# ESC.net
KiCad netlist of a schematic drawn in EasyEDA Pro
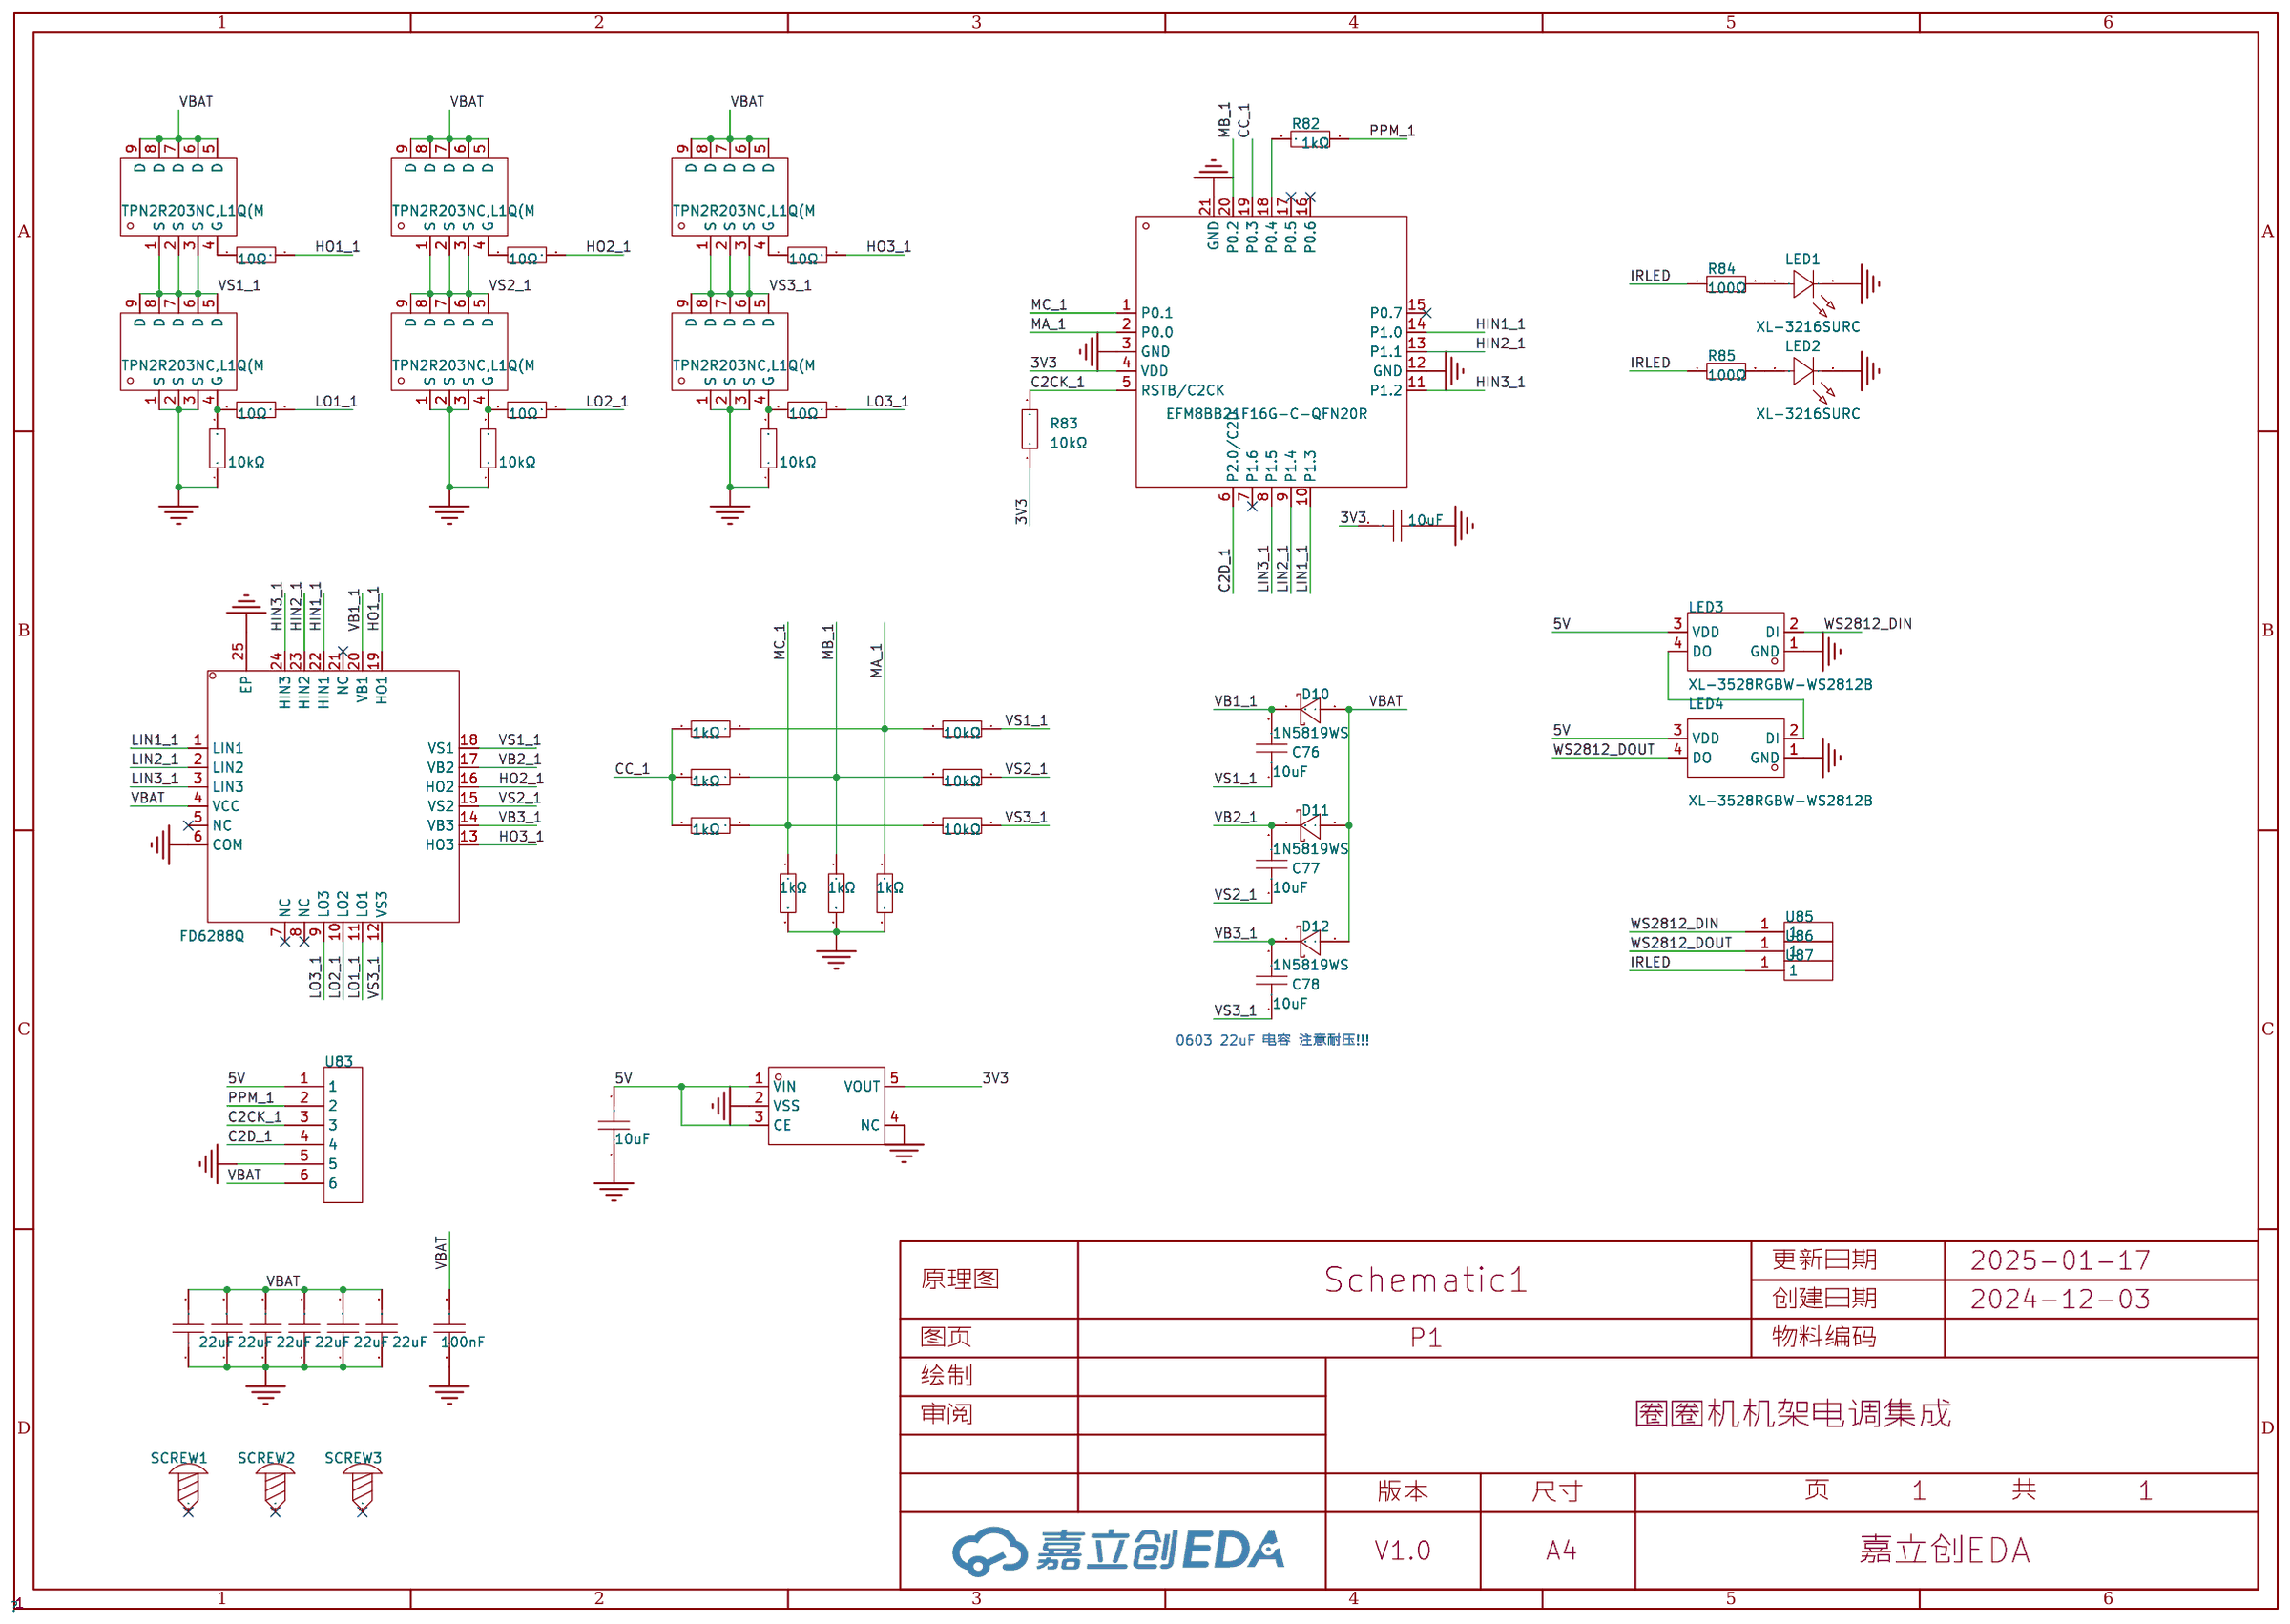
[diagram p0: schematic sheet]

(export (version "E")
  (design (tool "Eeschema 10.0.6"))
  (components
    (comp (ref "C6")
      (value "10uF")
      (footprint "easyedapro:C0603")
      (fields
        (field (name "Manufacturer Part") "CL10A106KP8NNNC")
        (field (name "Manufacturer") "SAMSUNG(三星)")
      )
      (libsource (lib "easyedapro") (part "CapAcitance"))
    )
    (comp (ref "C34")
      (value "100nF")
      (footprint "easyedapro:C0603")
      (fields
        (field (name "Manufacturer Part") "CC0603KRX7R9BB104")
        (field (name "Manufacturer") "YAGEO(国巨)")
      )
      (libsource (lib "easyedapro") (part "CapAcitance"))
    )
    (comp (ref "C45")
      (value "22uF")
      (footprint "easyedapro:C0805")
      (description "容值:22uF;精度:±20%;额定电压:25V;材质(温度系数):X5R;")
      (fields
        (field (name "Manufacturer Part") "CL21A226MAQNNNE")
        (field (name "Manufacturer") "SAMSUNG(三星)")
      )
      (libsource (lib "easyedapro") (part "CL21A226MAQNNNE"))
    )
    (comp (ref "C73")
      (value "22uF")
      (footprint "easyedapro:C0805")
      (description "容值:22uF;精度:±20%;额定电压:25V;材质(温度系数):X5R;")
      (fields
        (field (name "Manufacturer Part") "CL21A226MAQNNNE")
        (field (name "Manufacturer") "SAMSUNG(三星)")
      )
      (libsource (lib "easyedapro") (part "CL21A226MAQNNNE"))
    )
    (comp (ref "C74")
      (value "22uF")
      (footprint "easyedapro:C0805")
      (description "容值:22uF;精度:±20%;额定电压:25V;材质(温度系数):X5R;")
      (fields
        (field (name "Manufacturer Part") "CL21A226MAQNNNE")
        (field (name "Manufacturer") "SAMSUNG(三星)")
      )
      (libsource (lib "easyedapro") (part "CL21A226MAQNNNE"))
    )
    (comp (ref "C75")
      (value "10uF")
      (footprint "easyedapro:C0603")
      (fields
        (field (name "Manufacturer Part") "CL10A106KP8NNNC")
        (field (name "Manufacturer") "SAMSUNG(三星)")
      )
      (libsource (lib "easyedapro") (part "CapAcitance"))
    )
    (comp (ref "C76")
      (value "10uF")
      (footprint "easyedapro:C0603")
      (fields
        (field (name "Manufacturer Part") "CL10A106MA8NRNC")
        (field (name "Manufacturer") "SAMSUNG(三星)")
      )
      (libsource (lib "easyedapro") (part "CapAcitance"))
    )
    (comp (ref "C77")
      (value "10uF")
      (footprint "easyedapro:C0603")
      (fields
        (field (name "Manufacturer Part") "CL10A106MA8NRNC")
        (field (name "Manufacturer") "SAMSUNG(三星)")
      )
      (libsource (lib "easyedapro") (part "CapAcitance"))
    )
    (comp (ref "C78")
      (value "10uF")
      (footprint "easyedapro:C0603")
      (fields
        (field (name "Manufacturer Part") "CL10A106MA8NRNC")
        (field (name "Manufacturer") "SAMSUNG(三星)")
      )
      (libsource (lib "easyedapro") (part "CapAcitance"))
    )
    (comp (ref "C79")
      (value "22uF")
      (footprint "easyedapro:C0805")
      (description "容值:22uF;精度:±20%;额定电压:25V;材质(温度系数):X5R;")
      (fields
        (field (name "Manufacturer Part") "CL21A226MAQNNNE")
        (field (name "Manufacturer") "SAMSUNG(三星)")
      )
      (libsource (lib "easyedapro") (part "CL21A226MAQNNNE"))
    )
    (comp (ref "C80")
      (value "22uF")
      (footprint "easyedapro:C0805")
      (description "容值:22uF;精度:±20%;额定电压:25V;材质(温度系数):X5R;")
      (fields
        (field (name "Manufacturer Part") "CL21A226MAQNNNE")
        (field (name "Manufacturer") "SAMSUNG(三星)")
      )
      (libsource (lib "easyedapro") (part "CL21A226MAQNNNE"))
    )
    (comp (ref "C81")
      (value "22uF")
      (footprint "easyedapro:C0805")
      (description "容值:22uF;精度:±20%;额定电压:25V;材质(温度系数):X5R;")
      (fields
        (field (name "Manufacturer Part") "CL21A226MAQNNNE")
        (field (name "Manufacturer") "SAMSUNG(三星)")
      )
      (libsource (lib "easyedapro") (part "CL21A226MAQNNNE"))
    )
    (comp (ref "D10")
      (value "1N5819WS")
      (footprint "easyedapro:SOD-323_L1.8-W1.3-LS2.5-RD")
      (description "正向压降(Vf):600mV@1A;直流反向耐压(Vr):40V;平均整流电流(Io):1A;")
      (fields (field (name "Manufacturer") "Hottech(合科泰)"))
      (libsource (lib "easyedapro") (part "1N5819WS"))
    )
    (comp (ref "D11")
      (value "1N5819WS")
      (footprint "easyedapro:SOD-323_L1.8-W1.3-LS2.5-RD")
      (description "正向压降(Vf):600mV@1A;直流反向耐压(Vr):40V;平均整流电流(Io):1A;")
      (fields (field (name "Manufacturer") "Hottech(合科泰)"))
      (libsource (lib "easyedapro") (part "1N5819WS"))
    )
    (comp (ref "D12")
      (value "1N5819WS")
      (footprint "easyedapro:SOD-323_L1.8-W1.3-LS2.5-RD")
      (description "正向压降(Vf):600mV@1A;直流反向耐压(Vr):40V;平均整流电流(Io):1A;")
      (fields (field (name "Manufacturer") "Hottech(合科泰)"))
      (libsource (lib "easyedapro") (part "1N5819WS"))
    )
    (comp (ref "LED1")
      (value "XL-3216SURC")
      (footprint "easyedapro:LED1206-R-RD_RED")
      (description "发光颜色:红色;功率:55mW;正向电流:25mA;主波长:617nm~621nm;透镜颜色:无色透明透镜;色温:-;发光角度:120°;载带方式:正贴;工作温度:-30°C~+85°C;")
      (fields (field (name "Manufacturer") "XINGLIGHT(成兴光)"))
      (libsource (lib "easyedapro") (part "XL-3216SURC"))
    )
    (comp (ref "LED2")
      (value "XL-3216SURC")
      (footprint "easyedapro:LED1206-R-RD_RED")
      (description "发光颜色:红色;功率:55mW;正向电流:25mA;主波长:617nm~621nm;透镜颜色:无色透明透镜;色温:-;发光角度:120°;载带方式:正贴;工作温度:-30°C~+85°C;")
      (fields (field (name "Manufacturer") "XINGLIGHT(成兴光)"))
      (libsource (lib "easyedapro") (part "XL-3216SURC"))
    )
    (comp (ref "LED3")
      (value "XL-3528RGBW-WS2812B")
      (footprint "easyedapro:LED-SMD_4P-L3.5-W2.8-BR-1")
      (description "3528 七彩幻彩雾状 ws2812B 内置驱动IC")
      (fields (field (name "Manufacturer") "XINGLIGHT(成兴光)"))
      (libsource (lib "easyedapro") (part "XL-3528RGBW-WS2812B"))
    )
    (comp (ref "LED4")
      (value "XL-3528RGBW-WS2812B")
      (footprint "easyedapro:LED-SMD_4P-L3.5-W2.8-BR-1")
      (description "3528 七彩幻彩雾状 ws2812B 内置驱动IC")
      (fields (field (name "Manufacturer") "XINGLIGHT(成兴光)"))
      (libsource (lib "easyedapro") (part "XL-3528RGBW-WS2812B"))
    )
    (comp (ref "Q7")
      (value "TPN2R203NC,L1Q(M")
      (footprint "easyedapro:TSON-8_L3.1-W3.1-P0.65-LS3.3-BL-EP")
      (fields (field (name "Manufacturer") "TOSHIBA(东芝)"))
      (libsource (lib "easyedapro") (part "TPN2R203NC,L1Q(M"))
    )
    (comp (ref "Q8")
      (value "TPN2R203NC,L1Q(M")
      (footprint "easyedapro:TSON-8_L3.1-W3.1-P0.65-LS3.3-BL-EP")
      (fields (field (name "Manufacturer") "TOSHIBA(东芝)"))
      (libsource (lib "easyedapro") (part "TPN2R203NC,L1Q(M"))
    )
    (comp (ref "Q9")
      (value "TPN2R203NC,L1Q(M")
      (footprint "easyedapro:TSON-8_L3.1-W3.1-P0.65-LS3.3-BL-EP")
      (fields (field (name "Manufacturer") "TOSHIBA(东芝)"))
      (libsource (lib "easyedapro") (part "TPN2R203NC,L1Q(M"))
    )
    (comp (ref "Q10")
      (value "TPN2R203NC,L1Q(M")
      (footprint "easyedapro:TSON-8_L3.1-W3.1-P0.65-LS3.3-BL-EP")
      (fields (field (name "Manufacturer") "TOSHIBA(东芝)"))
      (libsource (lib "easyedapro") (part "TPN2R203NC,L1Q(M"))
    )
    (comp (ref "Q11")
      (value "TPN2R203NC,L1Q(M")
      (footprint "easyedapro:TSON-8_L3.1-W3.1-P0.65-LS3.3-BL-EP")
      (fields (field (name "Manufacturer") "TOSHIBA(东芝)"))
      (libsource (lib "easyedapro") (part "TPN2R203NC,L1Q(M"))
    )
    (comp (ref "Q12")
      (value "TPN2R203NC,L1Q(M")
      (footprint "easyedapro:TSON-8_L3.1-W3.1-P0.65-LS3.3-BL-EP")
      (fields (field (name "Manufacturer") "TOSHIBA(东芝)"))
      (libsource (lib "easyedapro") (part "TPN2R203NC,L1Q(M"))
    )
    (comp (ref "R62")
      (value "10Ω")
      (footprint "easyedapro:R0402")
      (fields
        (field (name "Manufacturer Part") "0402WGF100JTCE")
        (field (name "Manufacturer") "UNI-ROYAL(厚声)")
      )
      (libsource (lib "easyedapro") (part "电阻"))
    )
    (comp (ref "R63")
      (value "10Ω")
      (footprint "easyedapro:R0402")
      (fields
        (field (name "Manufacturer Part") "0402WGF100JTCE")
        (field (name "Manufacturer") "UNI-ROYAL(厚声)")
      )
      (libsource (lib "easyedapro") (part "电阻"))
    )
    (comp (ref "R64")
      (value "10Ω")
      (footprint "easyedapro:R0402")
      (fields
        (field (name "Manufacturer Part") "0402WGF100JTCE")
        (field (name "Manufacturer") "UNI-ROYAL(厚声)")
      )
      (libsource (lib "easyedapro") (part "电阻"))
    )
    (comp (ref "R65")
      (value "10Ω")
      (footprint "easyedapro:R0402")
      (fields
        (field (name "Manufacturer Part") "0402WGF100JTCE")
        (field (name "Manufacturer") "UNI-ROYAL(厚声)")
      )
      (libsource (lib "easyedapro") (part "电阻"))
    )
    (comp (ref "R66")
      (value "10Ω")
      (footprint "easyedapro:R0402")
      (fields
        (field (name "Manufacturer Part") "0402WGF100JTCE")
        (field (name "Manufacturer") "UNI-ROYAL(厚声)")
      )
      (libsource (lib "easyedapro") (part "电阻"))
    )
    (comp (ref "R67")
      (value "10Ω")
      (footprint "easyedapro:R0402")
      (fields
        (field (name "Manufacturer Part") "0402WGF100JTCE")
        (field (name "Manufacturer") "UNI-ROYAL(厚声)")
      )
      (libsource (lib "easyedapro") (part "电阻"))
    )
    (comp (ref "R68")
      (value "10kΩ")
      (footprint "easyedapro:R0402")
      (fields
        (field (name "Manufacturer Part") "0402WGF1002TCE")
        (field (name "Manufacturer") "UNI-ROYAL(厚声)")
      )
      (libsource (lib "easyedapro") (part "电阻"))
    )
    (comp (ref "R69")
      (value "10kΩ")
      (footprint "easyedapro:R0402")
      (fields
        (field (name "Manufacturer Part") "0402WGF1002TCE")
        (field (name "Manufacturer") "UNI-ROYAL(厚声)")
      )
      (libsource (lib "easyedapro") (part "电阻"))
    )
    (comp (ref "R70")
      (value "10kΩ")
      (footprint "easyedapro:R0402")
      (fields
        (field (name "Manufacturer Part") "0402WGF1002TCE")
        (field (name "Manufacturer") "UNI-ROYAL(厚声)")
      )
      (libsource (lib "easyedapro") (part "电阻"))
    )
    (comp (ref "R71")
      (value "10kΩ")
      (footprint "easyedapro:R0402")
      (fields
        (field (name "Manufacturer Part") "0402WGF1002TCE")
        (field (name "Manufacturer") "UNI-ROYAL(厚声)")
      )
      (libsource (lib "easyedapro") (part "电阻"))
    )
    (comp (ref "R72")
      (value "10kΩ")
      (footprint "easyedapro:R0402")
      (fields
        (field (name "Manufacturer Part") "0402WGF1002TCE")
        (field (name "Manufacturer") "UNI-ROYAL(厚声)")
      )
      (libsource (lib "easyedapro") (part "电阻"))
    )
    (comp (ref "R73")
      (value "10kΩ")
      (footprint "easyedapro:R0402")
      (fields
        (field (name "Manufacturer Part") "0402WGF1002TCE")
        (field (name "Manufacturer") "UNI-ROYAL(厚声)")
      )
      (libsource (lib "easyedapro") (part "电阻"))
    )
    (comp (ref "R74")
      (value "1kΩ")
      (footprint "easyedapro:R0402")
      (fields
        (field (name "Manufacturer Part") "0402WGF1001TCE")
        (field (name "Manufacturer") "UNI-ROYAL(厚声)")
      )
      (libsource (lib "easyedapro") (part "电阻"))
    )
    (comp (ref "R75")
      (value "1kΩ")
      (footprint "easyedapro:R0402")
      (fields
        (field (name "Manufacturer Part") "0402WGF1001TCE")
        (field (name "Manufacturer") "UNI-ROYAL(厚声)")
      )
      (libsource (lib "easyedapro") (part "电阻"))
    )
    (comp (ref "R76")
      (value "1kΩ")
      (footprint "easyedapro:R0402")
      (fields
        (field (name "Manufacturer Part") "0402WGF1001TCE")
        (field (name "Manufacturer") "UNI-ROYAL(厚声)")
      )
      (libsource (lib "easyedapro") (part "电阻"))
    )
    (comp (ref "R77")
      (value "1kΩ")
      (footprint "easyedapro:R0402")
      (fields
        (field (name "Manufacturer Part") "0402WGF1001TCE")
        (field (name "Manufacturer") "UNI-ROYAL(厚声)")
      )
      (libsource (lib "easyedapro") (part "电阻"))
    )
    (comp (ref "R78")
      (value "1kΩ")
      (footprint "easyedapro:R0402")
      (fields
        (field (name "Manufacturer Part") "0402WGF1001TCE")
        (field (name "Manufacturer") "UNI-ROYAL(厚声)")
      )
      (libsource (lib "easyedapro") (part "电阻"))
    )
    (comp (ref "R79")
      (value "1kΩ")
      (footprint "easyedapro:R0402")
      (fields
        (field (name "Manufacturer Part") "0402WGF1001TCE")
        (field (name "Manufacturer") "UNI-ROYAL(厚声)")
      )
      (libsource (lib "easyedapro") (part "电阻"))
    )
    (comp (ref "R82")
      (value "1kΩ")
      (footprint "easyedapro:R0402")
      (fields
        (field (name "Manufacturer Part") "0603WAF1001T5E")
        (field (name "Manufacturer") "UNI-ROYAL(厚声)")
      )
      (libsource (lib "easyedapro") (part "电阻"))
    )
    (comp (ref "R83")
      (value "10kΩ")
      (footprint "easyedapro:R0402")
      (fields
        (field (name "Manufacturer Part") "0603WAF1002T5E")
        (field (name "Manufacturer") "UNI-ROYAL(厚声)")
      )
      (libsource (lib "easyedapro") (part "电阻"))
    )
    (comp (ref "R84")
      (value "100Ω")
      (footprint "easyedapro:R0402")
      (fields
        (field (name "Manufacturer Part") "0603WAF1000T5E")
        (field (name "Manufacturer") "UNI-ROYAL(厚声)")
      )
      (libsource (lib "easyedapro") (part "电阻"))
    )
    (comp (ref "R85")
      (value "100Ω")
      (footprint "easyedapro:R0402")
      (fields
        (field (name "Manufacturer Part") "0603WAF1000T5E")
        (field (name "Manufacturer") "UNI-ROYAL(厚声)")
      )
      (libsource (lib "easyedapro") (part "电阻"))
    )
    (comp (ref "SCREW1")
      (value "~")
      (footprint "easyedapro:M2螺丝")
      (libsource (lib "easyedapro") (part "螺丝孔"))
    )
    (comp (ref "SCREW2")
      (value "~")
      (footprint "easyedapro:M2螺丝")
      (libsource (lib "easyedapro") (part "螺丝孔"))
    )
    (comp (ref "SCREW3")
      (value "~")
      (footprint "easyedapro:M2螺丝")
      (libsource (lib "easyedapro") (part "螺丝孔"))
    )
    (comp (ref "U2")
      (value "EFM8BB21F16G-C-QFN20R")
      (footprint "easyedapro:QFN-20_L3.0-W3.0-P0.50-BL-EP1.7_EFM8BB21F16G")
      (description "CPU内核:51系列;程序存储容量:16KB;RAM总容量:2.25KB;GPIO端口数量:16;工作电压范围:2.2V~3.6V;CPU最大主频:50MHz;程序存储器类型:FLASH;")
      (fields (field (name "Manufacturer") "SKYWORKS/SILICON LABS(芯科)"))
      (libsource (lib "easyedapro") (part "EFM8BB21F16G-C-QFN20"))
    )
    (comp (ref "U79")
      (value "ME6217C33M5G")
      (footprint "easyedapro:SOT-23-5_L3.0-W1.7-P0.95-LS2.8-BR")
      (description "输出类型:固定;输出极性:正;最大输入电压:7V;输出电压:3.3V;输出电流:800mA;电源纹波抑制比(PSRR):65dB@(1kHz);")
      (fields (field (name "Manufacturer") "MICRONE(南京微盟)"))
      (libsource (lib "easyedapro") (part "ME6217C33M5G"))
    )
    (comp (ref "U82")
      (value "FD6288Q")
      (footprint "easyedapro:QFN-24_L4.0-W4.0-P0.50-BL-EP2.6")
      (fields (field (name "Manufacturer") "Fortior Tech(峰岹)"))
      (libsource (lib "easyedapro") (part "FD6288Q_C328453"))
    )
    (comp (ref "U83")
      (value "~")
      (footprint "easyedapro:6pin焊接引出")
      (libsource (lib "easyedapro") (part "6pin焊接引出"))
    )
    (comp (ref "U85")
      (value "~")
      (footprint "easyedapro:1pin焊接引出")
      (libsource (lib "easyedapro") (part "1pin焊接引出"))
    )
    (comp (ref "U86")
      (value "~")
      (footprint "easyedapro:1pin焊接引出")
      (libsource (lib "easyedapro") (part "1pin焊接引出"))
    )
    (comp (ref "U87")
      (value "~")
      (footprint "easyedapro:1pin焊接引出")
      (libsource (lib "easyedapro") (part "1pin焊接引出"))
    )
  )
  (nets
    (net (code "1") (name "/3V3") (class "Default")
      (node (ref "C6") (pin "2") (pinfunction "2_2") (pintype "input"))
      (node (ref "R83") (pin "1") (pinfunction "1_1") (pintype "input"))
      (node (ref "U2") (pin "4") (pinfunction "VDD_4") (pintype "unspecified"))
      (node (ref "U79") (pin "5") (pinfunction "VOUT_5") (pintype "input"))
    )
    (net (code "2") (name "/5V") (class "Default")
      (node (ref "C75") (pin "2") (pinfunction "2_2") (pintype "input"))
      (node (ref "LED3") (pin "3") (pinfunction "VDD_3") (pintype "unspecified"))
      (node (ref "LED4") (pin "3") (pinfunction "VDD_3") (pintype "unspecified"))
      (node (ref "U79") (pin "1") (pinfunction "VIN_1") (pintype "input"))
      (node (ref "U79") (pin "3") (pinfunction "CE_3") (pintype "input"))
      (node (ref "U83") (pin "1") (pinfunction "1_1") (pintype "input"))
    )
    (net (code "3") (name "/C2CK_1") (class "Default")
      (node (ref "R83") (pin "2") (pinfunction "2_2") (pintype "input"))
      (node (ref "U2") (pin "5") (pinfunction "RSTB/C2CK_5") (pintype "unspecified"))
      (node (ref "U83") (pin "3") (pinfunction "3_3") (pintype "input"))
    )
    (net (code "4") (name "/C2D_1") (class "Default")
      (node (ref "U2") (pin "6") (pinfunction "P2.0/C2D_6") (pintype "unspecified"))
      (node (ref "U83") (pin "4") (pinfunction "4_4") (pintype "input"))
    )
    (net (code "5") (name "/CC_1") (class "Default")
      (node (ref "R74") (pin "2") (pinfunction "2_2") (pintype "input"))
      (node (ref "R75") (pin "2") (pinfunction "2_2") (pintype "input"))
      (node (ref "R76") (pin "2") (pinfunction "2_2") (pintype "input"))
      (node (ref "U2") (pin "19") (pinfunction "P0.3_19") (pintype "unspecified"))
    )
    (net (code "6") (name "/HIN1_1") (class "Default")
      (node (ref "U2") (pin "14") (pinfunction "P1.0_14") (pintype "unspecified"))
      (node (ref "U82") (pin "22") (pinfunction "HIN1_22") (pintype "unspecified"))
    )
    (net (code "7") (name "/HIN2_1") (class "Default")
      (node (ref "U2") (pin "13") (pinfunction "P1.1_13") (pintype "unspecified"))
      (node (ref "U82") (pin "23") (pinfunction "HIN2_23") (pintype "unspecified"))
    )
    (net (code "8") (name "/HIN3_1") (class "Default")
      (node (ref "U2") (pin "11") (pinfunction "P1.2_11") (pintype "unspecified"))
      (node (ref "U82") (pin "24") (pinfunction "HIN3_24") (pintype "unspecified"))
    )
    (net (code "9") (name "/HO1_1") (class "Default")
      (node (ref "R62") (pin "2") (pinfunction "2_2") (pintype "input"))
      (node (ref "U82") (pin "19") (pinfunction "HO1_19") (pintype "unspecified"))
    )
    (net (code "10") (name "/HO2_1") (class "Default")
      (node (ref "R63") (pin "2") (pinfunction "2_2") (pintype "input"))
      (node (ref "U82") (pin "16") (pinfunction "HO2_16") (pintype "unspecified"))
    )
    (net (code "11") (name "/HO3_1") (class "Default")
      (node (ref "R64") (pin "2") (pinfunction "2_2") (pintype "input"))
      (node (ref "U82") (pin "13") (pinfunction "HO3_13") (pintype "unspecified"))
    )
    (net (code "12") (name "/IRLED") (class "Default")
      (node (ref "R84") (pin "1") (pinfunction "1_1") (pintype "input"))
      (node (ref "R85") (pin "1") (pinfunction "1_1") (pintype "input"))
      (node (ref "U87") (pin "1") (pinfunction "1_1") (pintype "input"))
    )
    (net (code "13") (name "/LIN1_1") (class "Default")
      (node (ref "U2") (pin "10") (pinfunction "P1.3_10") (pintype "unspecified"))
      (node (ref "U82") (pin "1") (pinfunction "LIN1_1") (pintype "unspecified"))
    )
    (net (code "14") (name "/LIN2_1") (class "Default")
      (node (ref "U2") (pin "9") (pinfunction "P1.4_9") (pintype "unspecified"))
      (node (ref "U82") (pin "2") (pinfunction "LIN2_2") (pintype "unspecified"))
    )
    (net (code "15") (name "/LIN3_1") (class "Default")
      (node (ref "U2") (pin "8") (pinfunction "P1.5_8") (pintype "unspecified"))
      (node (ref "U82") (pin "3") (pinfunction "LIN3_3") (pintype "unspecified"))
    )
    (net (code "16") (name "/LO1_1") (class "Default")
      (node (ref "R67") (pin "2") (pinfunction "2_2") (pintype "input"))
      (node (ref "U82") (pin "11") (pinfunction "LO1_11") (pintype "unspecified"))
    )
    (net (code "17") (name "/LO2_1") (class "Default")
      (node (ref "R66") (pin "2") (pinfunction "2_2") (pintype "input"))
      (node (ref "U82") (pin "10") (pinfunction "LO2_10") (pintype "unspecified"))
    )
    (net (code "18") (name "/LO3_1") (class "Default")
      (node (ref "R65") (pin "2") (pinfunction "2_2") (pintype "input"))
      (node (ref "U82") (pin "9") (pinfunction "LO3_9") (pintype "unspecified"))
    )
    (net (code "19") (name "/MA_1") (class "Default")
      (node (ref "R71") (pin "2") (pinfunction "2_2") (pintype "input"))
      (node (ref "R74") (pin "1") (pinfunction "1_1") (pintype "input"))
      (node (ref "R79") (pin "1") (pinfunction "1_1") (pintype "input"))
      (node (ref "U2") (pin "2") (pinfunction "P0.0_2") (pintype "unspecified"))
    )
    (net (code "20") (name "/MB_1") (class "Default")
      (node (ref "R72") (pin "2") (pinfunction "2_2") (pintype "input"))
      (node (ref "R75") (pin "1") (pinfunction "1_1") (pintype "input"))
      (node (ref "R78") (pin "1") (pinfunction "1_1") (pintype "input"))
      (node (ref "U2") (pin "20") (pinfunction "P0.2_20") (pintype "unspecified"))
    )
    (net (code "21") (name "/MC_1") (class "Default")
      (node (ref "R73") (pin "2") (pinfunction "2_2") (pintype "input"))
      (node (ref "R76") (pin "1") (pinfunction "1_1") (pintype "input"))
      (node (ref "R77") (pin "1") (pinfunction "1_1") (pintype "input"))
      (node (ref "U2") (pin "1") (pinfunction "P0.1_1") (pintype "unspecified"))
    )
    (net (code "22") (name "/PPM_1") (class "Default")
      (node (ref "R82") (pin "2") (pinfunction "2_2") (pintype "input"))
      (node (ref "U83") (pin "2") (pinfunction "2_2") (pintype "input"))
    )
    (net (code "23") (name "/VB1_1") (class "Default")
      (node (ref "C76") (pin "2") (pinfunction "2_2") (pintype "input"))
      (node (ref "D10") (pin "1") (pinfunction "K_1") (pintype "unspecified"))
      (node (ref "U82") (pin "20") (pinfunction "VB1_20") (pintype "unspecified"))
    )
    (net (code "24") (name "/VB2_1") (class "Default")
      (node (ref "C77") (pin "2") (pinfunction "2_2") (pintype "input"))
      (node (ref "D11") (pin "1") (pinfunction "K_1") (pintype "unspecified"))
      (node (ref "U82") (pin "17") (pinfunction "VB2_17") (pintype "unspecified"))
    )
    (net (code "25") (name "/VB3_1") (class "Default")
      (node (ref "C78") (pin "2") (pinfunction "2_2") (pintype "input"))
      (node (ref "D12") (pin "1") (pinfunction "K_1") (pintype "unspecified"))
      (node (ref "U82") (pin "14") (pinfunction "VB3_14") (pintype "unspecified"))
    )
    (net (code "26") (name "/VBAT") (class "Default")
      (node (ref "C34") (pin "2") (pinfunction "2_2") (pintype "input"))
      (node (ref "C45") (pin "2") (pinfunction "2_2") (pintype "unspecified"))
      (node (ref "C73") (pin "2") (pinfunction "2_2") (pintype "unspecified"))
      (node (ref "C74") (pin "2") (pinfunction "2_2") (pintype "unspecified"))
      (node (ref "C79") (pin "2") (pinfunction "2_2") (pintype "unspecified"))
      (node (ref "C80") (pin "2") (pinfunction "2_2") (pintype "unspecified"))
      (node (ref "C81") (pin "2") (pinfunction "2_2") (pintype "unspecified"))
      (node (ref "D10") (pin "2") (pinfunction "A_2") (pintype "unspecified"))
      (node (ref "D11") (pin "2") (pinfunction "A_2") (pintype "unspecified"))
      (node (ref "D12") (pin "2") (pinfunction "A_2") (pintype "unspecified"))
      (node (ref "Q11") (pin "5") (pinfunction "D_5") (pintype "unspecified"))
      (node (ref "Q11") (pin "6") (pinfunction "D_6") (pintype "unspecified"))
      (node (ref "Q11") (pin "7") (pinfunction "D_7") (pintype "unspecified"))
      (node (ref "Q11") (pin "8") (pinfunction "D_8") (pintype "unspecified"))
      (node (ref "Q11") (pin "9") (pinfunction "D_9") (pintype "unspecified"))
      (node (ref "Q7") (pin "5") (pinfunction "D_5") (pintype "unspecified"))
      (node (ref "Q7") (pin "6") (pinfunction "D_6") (pintype "unspecified"))
      (node (ref "Q7") (pin "7") (pinfunction "D_7") (pintype "unspecified"))
      (node (ref "Q7") (pin "8") (pinfunction "D_8") (pintype "unspecified"))
      (node (ref "Q7") (pin "9") (pinfunction "D_9") (pintype "unspecified"))
      (node (ref "Q9") (pin "5") (pinfunction "D_5") (pintype "unspecified"))
      (node (ref "Q9") (pin "6") (pinfunction "D_6") (pintype "unspecified"))
      (node (ref "Q9") (pin "7") (pinfunction "D_7") (pintype "unspecified"))
      (node (ref "Q9") (pin "8") (pinfunction "D_8") (pintype "unspecified"))
      (node (ref "Q9") (pin "9") (pinfunction "D_9") (pintype "unspecified"))
      (node (ref "U82") (pin "4") (pinfunction "VCC_4") (pintype "unspecified"))
      (node (ref "U83") (pin "6") (pinfunction "6_6") (pintype "input"))
    )
    (net (code "27") (name "/VS1_1") (class "Default")
      (node (ref "C76") (pin "1") (pinfunction "1_1") (pintype "input"))
      (node (ref "Q7") (pin "1") (pinfunction "S_1") (pintype "unspecified"))
      (node (ref "Q7") (pin "2") (pinfunction "S_2") (pintype "unspecified"))
      (node (ref "Q7") (pin "3") (pinfunction "S_3") (pintype "unspecified"))
      (node (ref "Q8") (pin "5") (pinfunction "D_5") (pintype "unspecified"))
      (node (ref "Q8") (pin "6") (pinfunction "D_6") (pintype "unspecified"))
      (node (ref "Q8") (pin "7") (pinfunction "D_7") (pintype "unspecified"))
      (node (ref "Q8") (pin "8") (pinfunction "D_8") (pintype "unspecified"))
      (node (ref "Q8") (pin "9") (pinfunction "D_9") (pintype "unspecified"))
      (node (ref "R71") (pin "1") (pinfunction "1_1") (pintype "input"))
      (node (ref "U82") (pin "18") (pinfunction "VS1_18") (pintype "unspecified"))
    )
    (net (code "28") (name "/VS2_1") (class "Default")
      (node (ref "C77") (pin "1") (pinfunction "1_1") (pintype "input"))
      (node (ref "Q10") (pin "5") (pinfunction "D_5") (pintype "unspecified"))
      (node (ref "Q10") (pin "6") (pinfunction "D_6") (pintype "unspecified"))
      (node (ref "Q10") (pin "7") (pinfunction "D_7") (pintype "unspecified"))
      (node (ref "Q10") (pin "8") (pinfunction "D_8") (pintype "unspecified"))
      (node (ref "Q10") (pin "9") (pinfunction "D_9") (pintype "unspecified"))
      (node (ref "Q9") (pin "1") (pinfunction "S_1") (pintype "unspecified"))
      (node (ref "Q9") (pin "2") (pinfunction "S_2") (pintype "unspecified"))
      (node (ref "Q9") (pin "3") (pinfunction "S_3") (pintype "unspecified"))
      (node (ref "R72") (pin "1") (pinfunction "1_1") (pintype "input"))
      (node (ref "U82") (pin "15") (pinfunction "VS2_15") (pintype "unspecified"))
    )
    (net (code "29") (name "/VS3_1") (class "Default")
      (node (ref "C78") (pin "1") (pinfunction "1_1") (pintype "input"))
      (node (ref "Q11") (pin "1") (pinfunction "S_1") (pintype "unspecified"))
      (node (ref "Q11") (pin "2") (pinfunction "S_2") (pintype "unspecified"))
      (node (ref "Q11") (pin "3") (pinfunction "S_3") (pintype "unspecified"))
      (node (ref "Q12") (pin "5") (pinfunction "D_5") (pintype "unspecified"))
      (node (ref "Q12") (pin "6") (pinfunction "D_6") (pintype "unspecified"))
      (node (ref "Q12") (pin "7") (pinfunction "D_7") (pintype "unspecified"))
      (node (ref "Q12") (pin "8") (pinfunction "D_8") (pintype "unspecified"))
      (node (ref "Q12") (pin "9") (pinfunction "D_9") (pintype "unspecified"))
      (node (ref "R73") (pin "1") (pinfunction "1_1") (pintype "input"))
      (node (ref "U82") (pin "12") (pinfunction "VS3_12") (pintype "unspecified"))
    )
    (net (code "30") (name "/WS2812_DIN") (class "Default")
      (node (ref "LED3") (pin "2") (pinfunction "DI_2") (pintype "unspecified"))
      (node (ref "U85") (pin "1") (pinfunction "1_1") (pintype "input"))
    )
    (net (code "31") (name "/WS2812_DOUT") (class "Default")
      (node (ref "LED4") (pin "4") (pinfunction "DO_4") (pintype "unspecified"))
      (node (ref "U86") (pin "1") (pinfunction "1_1") (pintype "input"))
    )
    (net (code "32") (name "GND") (class "Default")
      (node (ref "C34") (pin "1") (pinfunction "1_1") (pintype "input"))
      (node (ref "C45") (pin "1") (pinfunction "1_1") (pintype "unspecified"))
      (node (ref "C6") (pin "1") (pinfunction "1_1") (pintype "input"))
      (node (ref "C73") (pin "1") (pinfunction "1_1") (pintype "unspecified"))
      (node (ref "C74") (pin "1") (pinfunction "1_1") (pintype "unspecified"))
      (node (ref "C75") (pin "1") (pinfunction "1_1") (pintype "input"))
      (node (ref "C79") (pin "1") (pinfunction "1_1") (pintype "unspecified"))
      (node (ref "C80") (pin "1") (pinfunction "1_1") (pintype "unspecified"))
      (node (ref "C81") (pin "1") (pinfunction "1_1") (pintype "unspecified"))
      (node (ref "LED1") (pin "2") (pinfunction "A_2") (pintype "unspecified"))
      (node (ref "LED2") (pin "2") (pinfunction "A_2") (pintype "unspecified"))
      (node (ref "LED3") (pin "1") (pinfunction "GND_1") (pintype "unspecified"))
      (node (ref "LED4") (pin "1") (pinfunction "GND_1") (pintype "unspecified"))
      (node (ref "Q10") (pin "1") (pinfunction "S_1") (pintype "unspecified"))
      (node (ref "Q10") (pin "2") (pinfunction "S_2") (pintype "unspecified"))
      (node (ref "Q10") (pin "3") (pinfunction "S_3") (pintype "unspecified"))
      (node (ref "Q12") (pin "1") (pinfunction "S_1") (pintype "unspecified"))
      (node (ref "Q12") (pin "2") (pinfunction "S_2") (pintype "unspecified"))
      (node (ref "Q12") (pin "3") (pinfunction "S_3") (pintype "unspecified"))
      (node (ref "Q8") (pin "1") (pinfunction "S_1") (pintype "unspecified"))
      (node (ref "Q8") (pin "2") (pinfunction "S_2") (pintype "unspecified"))
      (node (ref "Q8") (pin "3") (pinfunction "S_3") (pintype "unspecified"))
      (node (ref "R68") (pin "1") (pinfunction "1_1") (pintype "input"))
      (node (ref "R69") (pin "1") (pinfunction "1_1") (pintype "input"))
      (node (ref "R70") (pin "1") (pinfunction "1_1") (pintype "input"))
      (node (ref "R77") (pin "2") (pinfunction "2_2") (pintype "input"))
      (node (ref "R78") (pin "2") (pinfunction "2_2") (pintype "input"))
      (node (ref "R79") (pin "2") (pinfunction "2_2") (pintype "input"))
      (node (ref "U2") (pin "12") (pinfunction "GND_12") (pintype "unspecified"))
      (node (ref "U2") (pin "21") (pinfunction "GND_21") (pintype "unspecified"))
      (node (ref "U2") (pin "3") (pinfunction "GND_3") (pintype "unspecified"))
      (node (ref "U79") (pin "2") (pinfunction "VSS_2") (pintype "input"))
      (node (ref "U79") (pin "4") (pinfunction "NC_4") (pintype "input"))
      (node (ref "U82") (pin "25") (pinfunction "EP_25") (pintype "unspecified"))
      (node (ref "U82") (pin "6") (pinfunction "COM_6") (pintype "unspecified"))
      (node (ref "U83") (pin "5") (pinfunction "5_5") (pintype "input"))
    )
    (net (code "33") (name "Net-(LED1-K)") (class "Default")
      (node (ref "LED1") (pin "1") (pinfunction "K_1") (pintype "unspecified"))
      (node (ref "R84") (pin "2") (pinfunction "2_2") (pintype "input"))
    )
    (net (code "34") (name "Net-(LED2-K)") (class "Default")
      (node (ref "LED2") (pin "1") (pinfunction "K_1") (pintype "unspecified"))
      (node (ref "R85") (pin "2") (pinfunction "2_2") (pintype "input"))
    )
    (net (code "35") (name "Net-(LED3-DO)") (class "Default")
      (node (ref "LED3") (pin "4") (pinfunction "DO_4") (pintype "unspecified"))
      (node (ref "LED4") (pin "2") (pinfunction "DI_2") (pintype "unspecified"))
    )
    (net (code "36") (name "Net-(Q7-G)") (class "Default")
      (node (ref "Q7") (pin "4") (pinfunction "G_4") (pintype "unspecified"))
      (node (ref "R62") (pin "1") (pinfunction "1_1") (pintype "input"))
    )
    (net (code "37") (name "Net-(Q8-G)") (class "Default")
      (node (ref "Q8") (pin "4") (pinfunction "G_4") (pintype "unspecified"))
      (node (ref "R67") (pin "1") (pinfunction "1_1") (pintype "input"))
      (node (ref "R68") (pin "2") (pinfunction "2_2") (pintype "input"))
    )
    (net (code "38") (name "Net-(Q9-G)") (class "Default")
      (node (ref "Q9") (pin "4") (pinfunction "G_4") (pintype "unspecified"))
      (node (ref "R63") (pin "1") (pinfunction "1_1") (pintype "input"))
    )
    (net (code "39") (name "Net-(Q10-G)") (class "Default")
      (node (ref "Q10") (pin "4") (pinfunction "G_4") (pintype "unspecified"))
      (node (ref "R66") (pin "1") (pinfunction "1_1") (pintype "input"))
      (node (ref "R69") (pin "2") (pinfunction "2_2") (pintype "input"))
    )
    (net (code "40") (name "Net-(Q11-G)") (class "Default")
      (node (ref "Q11") (pin "4") (pinfunction "G_4") (pintype "unspecified"))
      (node (ref "R64") (pin "1") (pinfunction "1_1") (pintype "input"))
    )
    (net (code "41") (name "Net-(Q12-G)") (class "Default")
      (node (ref "Q12") (pin "4") (pinfunction "G_4") (pintype "unspecified"))
      (node (ref "R65") (pin "1") (pinfunction "1_1") (pintype "input"))
      (node (ref "R70") (pin "2") (pinfunction "2_2") (pintype "input"))
    )
    (net (code "42") (name "Net-(U2-P0.4)") (class "Default")
      (node (ref "R82") (pin "1") (pinfunction "1_1") (pintype "input"))
      (node (ref "U2") (pin "18") (pinfunction "P0.4_18") (pintype "unspecified"))
    )
    (net (code "43") (name "unconnected-(SCREW1-Pad1)") (class "Default")
      (node (ref "SCREW1") (pin "1") (pinfunction "1_1") (pintype "input+no_connect"))
    )
    (net (code "44") (name "unconnected-(SCREW2-Pad1)") (class "Default")
      (node (ref "SCREW2") (pin "1") (pinfunction "1_1") (pintype "input+no_connect"))
    )
    (net (code "45") (name "unconnected-(SCREW3-Pad1)") (class "Default")
      (node (ref "SCREW3") (pin "1") (pinfunction "1_1") (pintype "input+no_connect"))
    )
    (net (code "46") (name "unconnected-(U2-P0.5-Pad17)") (class "Default")
      (node (ref "U2") (pin "17") (pinfunction "P0.5_17") (pintype "unspecified+no_connect"))
    )
    (net (code "47") (name "unconnected-(U2-P0.6-Pad16)") (class "Default")
      (node (ref "U2") (pin "16") (pinfunction "P0.6_16") (pintype "unspecified+no_connect"))
    )
    (net (code "48") (name "unconnected-(U2-P0.7-Pad15)") (class "Default")
      (node (ref "U2") (pin "15") (pinfunction "P0.7_15") (pintype "unspecified+no_connect"))
    )
    (net (code "49") (name "unconnected-(U2-P1.6-Pad7)") (class "Default")
      (node (ref "U2") (pin "7") (pinfunction "P1.6_7") (pintype "unspecified+no_connect"))
    )
    (net (code "50") (name "unconnected-(U82-NC-Pad5)") (class "Default")
      (node (ref "U82") (pin "5") (pinfunction "NC_5") (pintype "unspecified+no_connect"))
    )
    (net (code "51") (name "unconnected-(U82-NC-Pad7)") (class "Default")
      (node (ref "U82") (pin "7") (pinfunction "NC_7") (pintype "unspecified+no_connect"))
    )
    (net (code "52") (name "unconnected-(U82-NC-Pad8)") (class "Default")
      (node (ref "U82") (pin "8") (pinfunction "NC_8") (pintype "unspecified+no_connect"))
    )
    (net (code "53") (name "unconnected-(U82-NC-Pad21)") (class "Default")
      (node (ref "U82") (pin "21") (pinfunction "NC_21") (pintype "unspecified+no_connect"))
    )
  )
)
